# Sheet1.net
KiCad netlist of a schematic drawn in Altium Designer
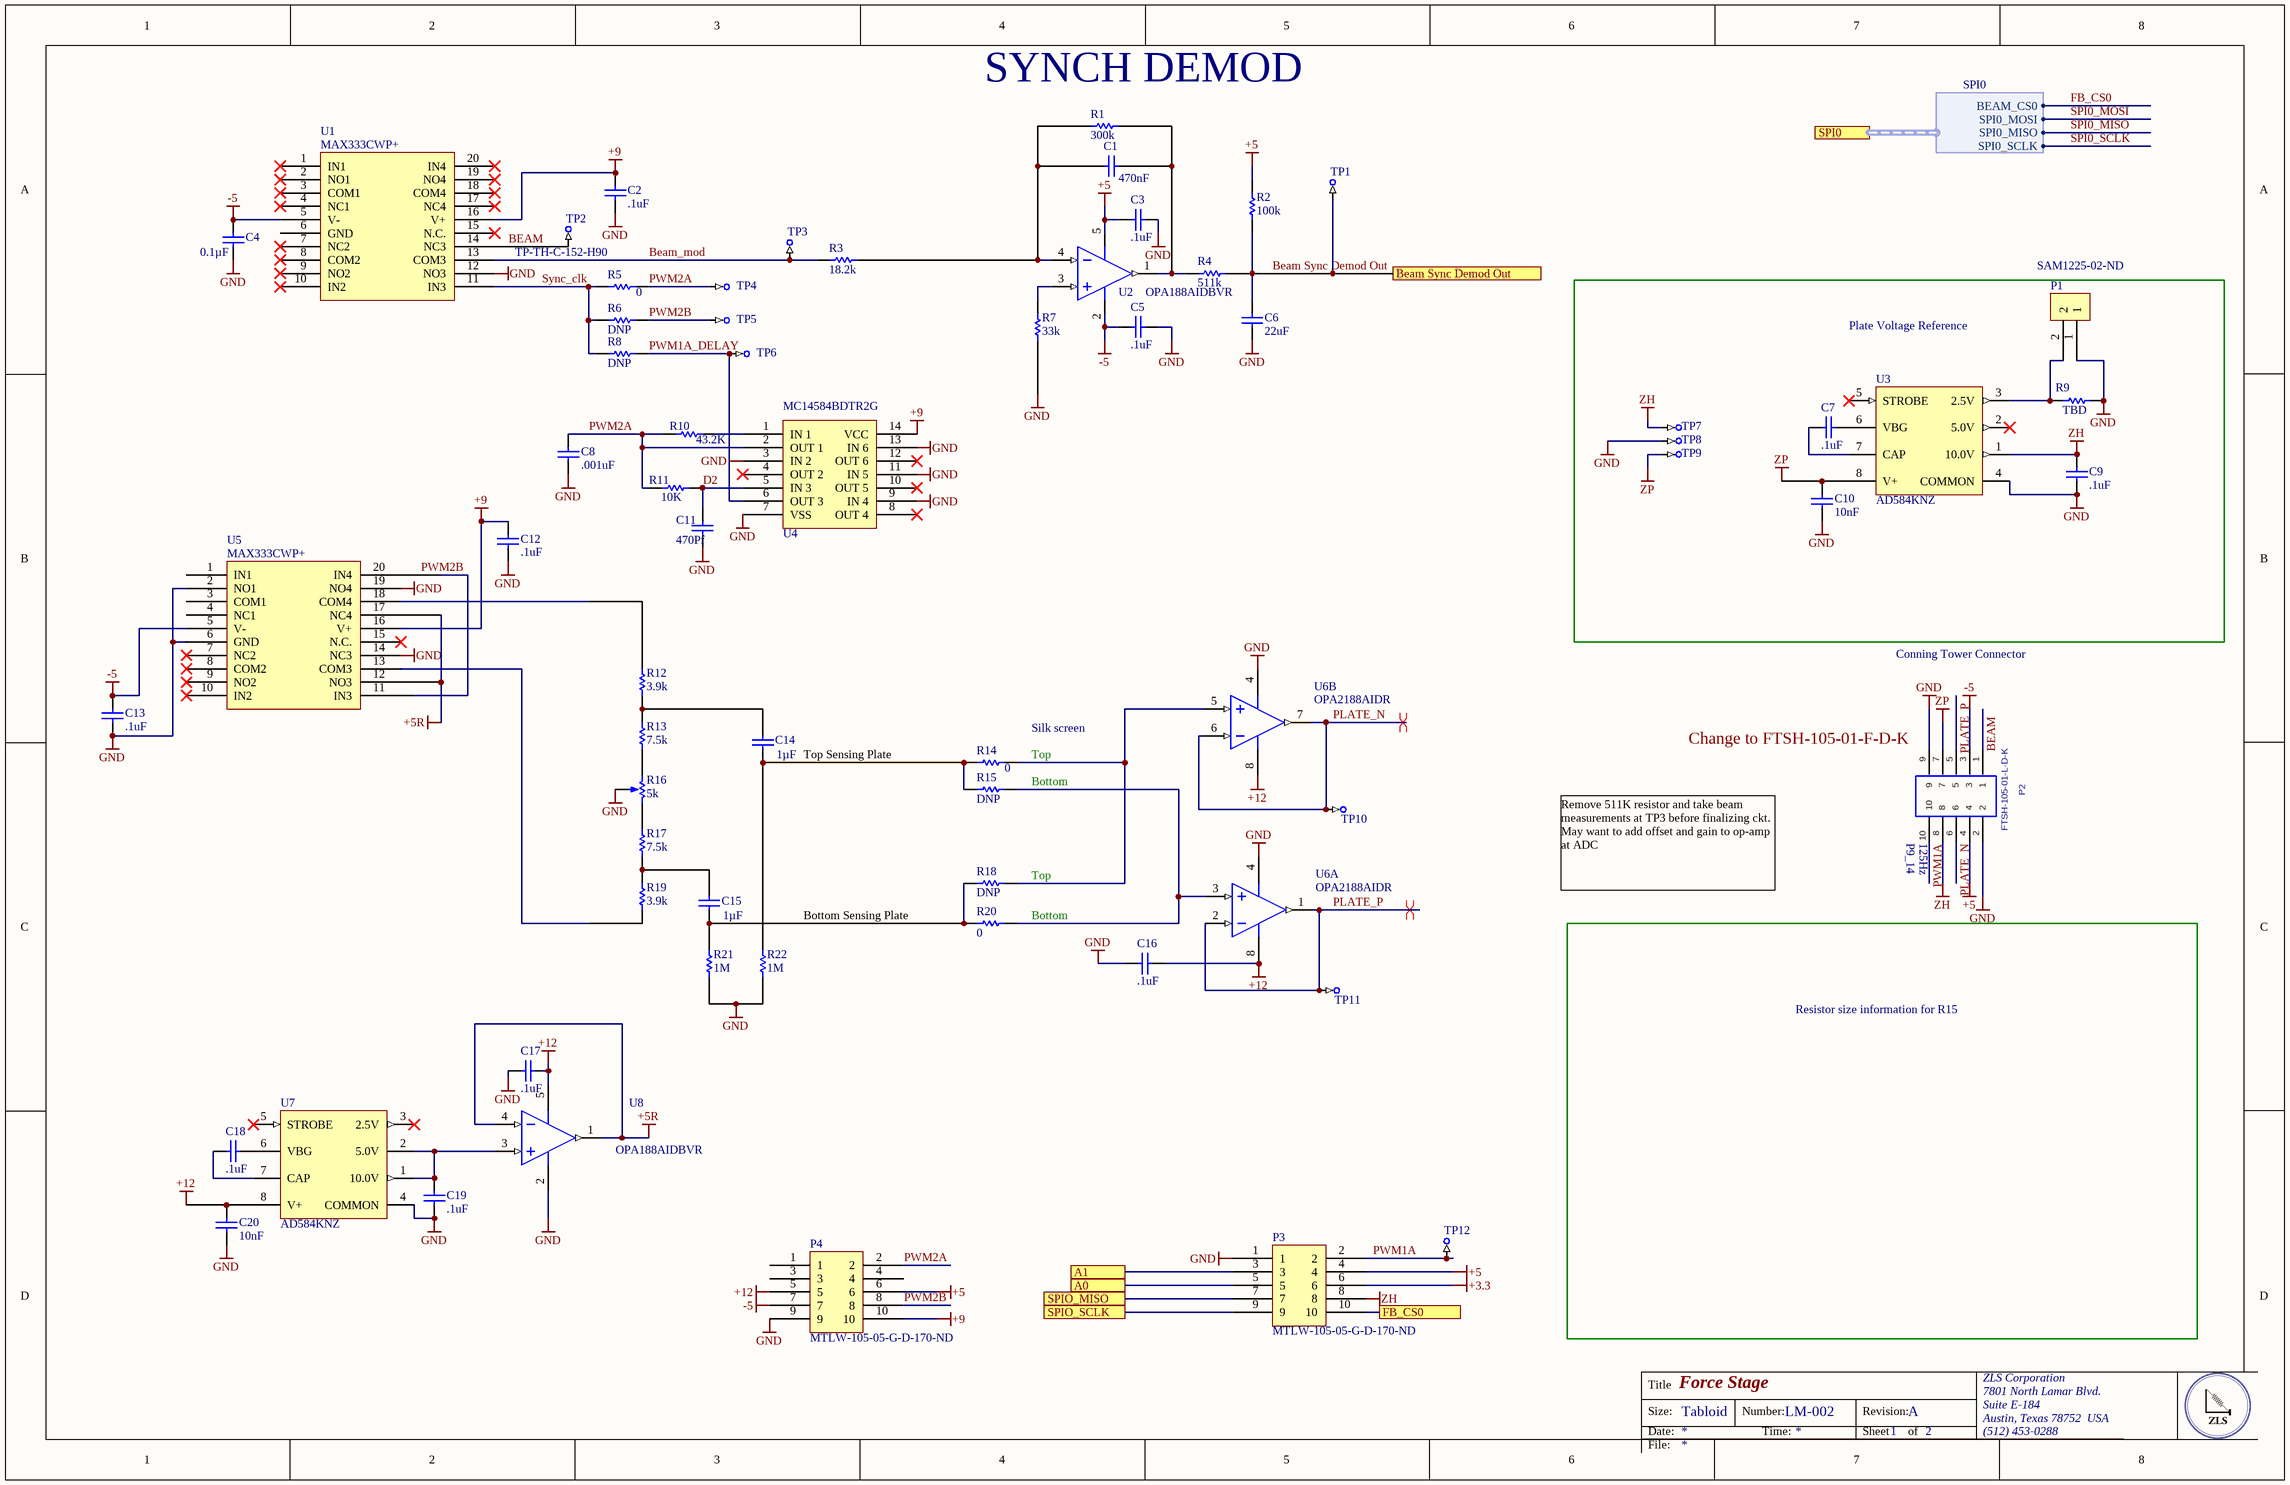
[diagram p0: Sheet1.SchDoc]

(export (version "E")
  (design (tool "Eeschema 10.0.6"))
  (components
    (comp (ref "C1")
      (value "470nF")
      (footprint "CAPC0805(2012)75_L")
      (description "CAP 150pF 16V ±10% 0805 (2012 Metric) Thickness 0.75mm SMD")
      (fields (field (name "TOLERANCE") "Â±10%"))
      (libsource (lib "Altium Content Vault") (part "CMP-1036-02117-1"))
    )
    (comp (ref "C2")
      (value ".1uF")
      (footprint "CAPC0805(2012)75_L")
      (description "CAP 150pF 16V ±10% 0805 (2012 Metric) Thickness 0.75mm SMD")
      (fields (field (name "TOLERANCE") "Â±10%"))
      (libsource (lib "Altium Content Vault") (part "CMP-1036-02117-1"))
    )
    (comp (ref "C3")
      (value ".1uF")
      (footprint "CAPC0805(2012)75_L")
      (description "CAP 150pF 16V ±10% 0805 (2012 Metric) Thickness 0.75mm SMD")
      (fields (field (name "TOLERANCE") "Â±10%"))
      (libsource (lib "Altium Content Vault") (part "CMP-1036-02117-1"))
    )
    (comp (ref "C4")
      (value "CAP CER 0.1UF 25V X7R 0805")
      (footprint "CAPC0805(2012)145_N")
      (fields
        (field (name "MANUFACTURER") "Murata Electronics North America")
        (field (name "MANUFACTURER PART NUMBER") "GRM21BR71E104KA01L")
        (field (name "CAPACITANCE") "0.1µF")
        (field (name "TOLERANCE") "±10%")
      )
      (libsource (lib "Altium Content Vault") (part "CMP-1036-04795-1"))
    )
    (comp (ref "C5")
      (value ".1uF")
      (footprint "CAPC0805(2012)75_L")
      (description "CAP 150pF 16V ±10% 0805 (2012 Metric) Thickness 0.75mm SMD")
      (fields (field (name "TOLERANCE") "Â±10%"))
      (libsource (lib "Altium Content Vault") (part "CMP-1036-02117-1"))
    )
    (comp (ref "C6")
      (value "22uF")
      (footprint "CAPC0805(2012)75_L")
      (description "CAP 150pF 16V ±10% 0805 (2012 Metric) Thickness 0.75mm SMD")
      (fields (field (name "TOLERANCE") "Â±10%"))
      (libsource (lib "Altium Content Vault") (part "CMP-1036-02117-1"))
    )
    (comp (ref "C7")
      (value ".1uF")
      (footprint "CAPC0805(2012)75_M")
      (description "CAP 33pF 25V ±2% 0805 (2012 Metric) Thickness 0.75mm SMD")
      (fields (field (name "TOLERANCE") "Â±2%"))
      (libsource (lib "Altium Content Vault") (part "CMP-1036-01414-1"))
    )
    (comp (ref "C8")
      (value ".001uF")
      (footprint "CAPC0805(2012)75_L")
      (description "CAP 150pF 16V ±10% 0805 (2012 Metric) Thickness 0.75mm SMD")
      (fields (field (name "TOLERANCE") "Â±10%"))
      (libsource (lib "Altium Content Vault") (part "CMP-1036-02117-1"))
    )
    (comp (ref "C9")
      (value ".1uF")
      (footprint "CAPC0805(2012)75_M")
      (description "CAP 33pF 25V ±2% 0805 (2012 Metric) Thickness 0.75mm SMD")
      (fields (field (name "TOLERANCE") "Â±2%"))
      (libsource (lib "Altium Content Vault") (part "CMP-1036-01414-1"))
    )
    (comp (ref "C10")
      (value "Multilayer Ceramic Capacitors MLCC - SMD/SMT 0.01uF 50volts 10% X7R")
      (footprint "CAPC0805(2012)145_N")
      (fields
        (field (name "MANUFACTURER") "Kemet")
        (field (name "MANUFACTURER PART NUMBER") "C0805C103K5RACAUTO")
        (field (name "CAPACITANCE") "10nF")
        (field (name "TOLERANCE") "10%")
      )
      (libsource (lib "Altium Content Vault") (part "CMP-1036-04795-1"))
    )
    (comp (ref "C11")
      (value "470Pf")
      (footprint "CAPC0805(2012)75_L")
      (description "CAP 150pF 16V ±10% 0805 (2012 Metric) Thickness 0.75mm SMD")
      (fields (field (name "TOLERANCE") "Â±10%"))
      (libsource (lib "Altium Content Vault") (part "CMP-1036-02117-1"))
    )
    (comp (ref "C12")
      (value ".1uF")
      (footprint "CAPC0805(2012)75_M")
      (description "CAP 33pF 25V ±2% 0805 (2012 Metric) Thickness 0.75mm SMD")
      (fields (field (name "TOLERANCE") "Â±2%"))
      (libsource (lib "Altium Content Vault") (part "CMP-1036-01414-1"))
    )
    (comp (ref "C13")
      (value ".1uF")
      (footprint "CAPC0805(2012)75_M")
      (description "CAP 33pF 25V ±2% 0805 (2012 Metric) Thickness 0.75mm SMD")
      (fields (field (name "TOLERANCE") "Â±2%"))
      (libsource (lib "Altium Content Vault") (part "CMP-1036-01414-1"))
    )
    (comp (ref "C14")
      (value "CAP CER 1UF 25V X7R 0805")
      (footprint "CAPC0805(2012)155_L")
      (fields
        (field (name "MANUFACTURER") "Murata Electronics North America")
        (field (name "MANUFACTURER PART NUMBER") "GRM21BR71E105KA99L")
        (field (name "CAPACITANCE") "1µF")
        (field (name "TOLERANCE") "±10%")
      )
      (libsource (lib "Altium Content Vault") (part "CMP-1036-04882-1"))
    )
    (comp (ref "C15")
      (value "CAP CER 1UF 25V X7R 0805")
      (footprint "CAPC0805(2012)155_L")
      (fields
        (field (name "MANUFACTURER") "Murata Electronics North America")
        (field (name "MANUFACTURER PART NUMBER") "GRM21BR71E105KA99L")
        (field (name "CAPACITANCE") "1µF")
        (field (name "TOLERANCE") "±10%")
      )
      (libsource (lib "Altium Content Vault") (part "CMP-1036-04882-1"))
    )
    (comp (ref "C16")
      (value ".1uF")
      (footprint "CAPC0805(2012)75_M")
      (description "CAP 33pF 25V ±2% 0805 (2012 Metric) Thickness 0.75mm SMD")
      (fields (field (name "TOLERANCE") "Â±2%"))
      (libsource (lib "Altium Content Vault") (part "CMP-1036-01414-1"))
    )
    (comp (ref "C17")
      (value ".1uF")
      (footprint "CAPC0805(2012)75_M")
      (description "CAP 33pF 25V ±2% 0805 (2012 Metric) Thickness 0.75mm SMD")
      (fields (field (name "TOLERANCE") "Â±2%"))
      (libsource (lib "Altium Content Vault") (part "CMP-1036-01414-1"))
    )
    (comp (ref "C18")
      (value ".1uF")
      (footprint "CAPC0805(2012)75_M")
      (description "CAP 33pF 25V ±2% 0805 (2012 Metric) Thickness 0.75mm SMD")
      (fields (field (name "TOLERANCE") "Â±2%"))
      (libsource (lib "Altium Content Vault") (part "CMP-1036-01414-1"))
    )
    (comp (ref "C19")
      (value ".1uF")
      (footprint "CAPC0805(2012)75_M")
      (description "CAP 33pF 25V ±2% 0805 (2012 Metric) Thickness 0.75mm SMD")
      (fields (field (name "TOLERANCE") "Â±2%"))
      (libsource (lib "Altium Content Vault") (part "CMP-1036-01414-1"))
    )
    (comp (ref "C20")
      (value "Multilayer Ceramic Capacitors MLCC - SMD/SMT 0.01uF 50volts 10% X7R")
      (footprint "CAPC0805(2012)145_N")
      (fields
        (field (name "MANUFACTURER") "Kemet")
        (field (name "MANUFACTURER PART NUMBER") "C0805C103K5RACAUTO")
        (field (name "CAPACITANCE") "10nF")
        (field (name "TOLERANCE") "10%")
      )
      (libsource (lib "Altium Content Vault") (part "CMP-1036-04795-1"))
    )
    (comp (ref "P1")
      (value "SSW-102-02-G-S-RA")
      (footprint "SSW-102-02-G-S-RA")
      (fields (field (name "SUPPLIER PART NUMBER 1") "SAM1225-02-ND"))
      (libsource (lib "ZLS_Schematic_lib") (part "SSW-102-02-G-S-RA"))
    )
    (comp (ref "P2")
      (value "FTSH-105-01-L-D-K")
      (footprint "FTSH-105-01-XXX-D-K")
      (description "TERMINAL STRIP, .050\"(1.27mm) PITCH, 10 PINS, KEYING OPTION.")
      (fields
        (field (name "MANUFACTURER") "SAMTEC")
        (field (name "CREATED") "September 26, 2016 - Wendy Xin")
      )
      (libsource (lib "FTSH-105-01-XXX-D-K") (part "FTSH-105-01-XXX-D-K"))
    )
    (comp (ref "P3")
      (value "TLW-105-05-G-D")
      (footprint "TLW-105-05-G-D")
      (fields
        (field (name "SUPPLIER PART NUMBER 1") "MTLW-105-05-G-D-170-ND")
        (field (name "MANUFACTURER") "Samtec Inc.")
        (field (name "MANUFACTURER PART NUMBER") "MTLW-105-05-G-D-170")
      )
      (libsource (lib "ZLS_Schematic_lib") (part "TLW-105-05-G-D"))
    )
    (comp (ref "P4")
      (value "TLW-105-05-G-D")
      (footprint "TLW-105-05-G-D")
      (fields
        (field (name "SUPPLIER PART NUMBER 1") "MTLW-105-05-G-D-170-ND")
        (field (name "MANUFACTURER") "Samtec Inc.")
        (field (name "MANUFACTURER PART NUMBER") "MTLW-105-05-G-D-170")
      )
      (libsource (lib "ZLS_Schematic_lib") (part "TLW-105-05-G-D"))
    )
    (comp (ref "R1")
      (value "300k")
      (footprint "RESC0805(2012)_L")
      (description "2R55 0.125W 1% 0805 (2012 Metric)  SMD")
      (fields (field (name "TOLERANCE") "1 %") (field (name "POWER") "0.125 W"))
      (libsource (lib "Altium Content Vault") (part "CMP-1013-00215-1"))
    )
    (comp (ref "R2")
      (value "100k")
      (footprint "RESC0805(2012)_L")
      (description "2R55 0.125W 1% 0805 (2012 Metric)  SMD")
      (fields (field (name "TOLERANCE") "1 %") (field (name "POWER") "0.125 W"))
      (libsource (lib "Altium Content Vault") (part "CMP-1013-00215-1"))
    )
    (comp (ref "R3")
      (value "18.2k")
      (footprint "RESC0805(2012)_L")
      (description "2R55 0.125W 1% 0805 (2012 Metric)  SMD")
      (fields (field (name "TOLERANCE") "1 %") (field (name "POWER") "0.125 W"))
      (libsource (lib "Altium Content Vault") (part "CMP-1013-00215-1"))
    )
    (comp (ref "R4")
      (value "511k")
      (footprint "RESC0805(2012)_L")
      (description "2R55 0.125W 1% 0805 (2012 Metric)  SMD")
      (fields (field (name "TOLERANCE") "1 %") (field (name "POWER") "0.125 W"))
      (libsource (lib "Altium Content Vault") (part "CMP-1013-00215-1"))
    )
    (comp (ref "R5")
      (value "0")
      (footprint "RESC0805(2012)_L")
      (description "2R55 0.125W 1% 0805 (2012 Metric)  SMD")
      (fields (field (name "TOLERANCE") "1 %") (field (name "POWER") "0.125 W"))
      (libsource (lib "Altium Content Vault") (part "CMP-1013-00215-1"))
    )
    (comp (ref "R6")
      (value "DNP")
      (footprint "RESC0805(2012)_L")
      (description "2R55 0.125W 1% 0805 (2012 Metric)  SMD")
      (fields (field (name "TOLERANCE") "1 %") (field (name "POWER") "0.125 W"))
      (libsource (lib "Altium Content Vault") (part "CMP-1013-00215-1"))
    )
    (comp (ref "R7")
      (value "33k")
      (footprint "RESC0805(2012)_L")
      (description "2R55 0.125W 1% 0805 (2012 Metric)  SMD")
      (fields (field (name "TOLERANCE") "1 %") (field (name "POWER") "0.125 W"))
      (libsource (lib "Altium Content Vault") (part "CMP-1013-00215-1"))
    )
    (comp (ref "R8")
      (value "DNP")
      (footprint "RESC0805(2012)_L")
      (description "2R55 0.125W 1% 0805 (2012 Metric)  SMD")
      (fields (field (name "TOLERANCE") "1 %") (field (name "POWER") "0.125 W"))
      (libsource (lib "Altium Content Vault") (part "CMP-1013-00215-1"))
    )
    (comp (ref "R9")
      (value "TBD")
      (footprint "VH102K")
      (libsource (lib "altium-import") (part "root_0_CMP-1013-00393-1_"))
    )
    (comp (ref "R10")
      (value "43.2K")
      (footprint "RESC0805(2012)_L")
      (description "2R55 0.125W 1% 0805 (2012 Metric)  SMD")
      (fields (field (name "TOLERANCE") "1 %") (field (name "POWER") "0.125 W"))
      (libsource (lib "Altium Content Vault") (part "CMP-1013-00215-1"))
    )
    (comp (ref "R11")
      (value "10K")
      (footprint "RESC0805(2012)_L")
      (description "2R55 0.125W 1% 0805 (2012 Metric)  SMD")
      (fields (field (name "TOLERANCE") "1 %") (field (name "POWER") "0.125 W"))
      (libsource (lib "Altium Content Vault") (part "CMP-1013-00215-1"))
    )
    (comp (ref "R12")
      (value "3.9k")
      (footprint "RESC0805(2012)_L")
      (description "2R55 0.125W 1% 0805 (2012 Metric)  SMD")
      (fields (field (name "TOLERANCE") "1 %") (field (name "POWER") "0.125 W"))
      (libsource (lib "Altium Content Vault") (part "CMP-1013-00215-1"))
    )
    (comp (ref "R13")
      (value "7.5k")
      (footprint "RESC0805(2012)_L")
      (description "2R55 0.125W 1% 0805 (2012 Metric)  SMD")
      (fields (field (name "TOLERANCE") "1 %") (field (name "POWER") "0.125 W"))
      (libsource (lib "Altium Content Vault") (part "CMP-1013-00215-1"))
    )
    (comp (ref "R14")
      (value "0")
      (footprint "RESC0805(2012)_L")
      (description "2R55 0.125W 1% 0805 (2012 Metric)  SMD")
      (fields (field (name "TOLERANCE") "1 %") (field (name "POWER") "0.125 W"))
      (libsource (lib "Altium Content Vault") (part "CMP-1013-00215-1"))
    )
    (comp (ref "R15")
      (value "DNP")
      (footprint "RESC0805(2012)_L")
      (description "2R55 0.125W 1% 0805 (2012 Metric)  SMD")
      (fields (field (name "TOLERANCE") "1 %") (field (name "POWER") "0.125 W"))
      (libsource (lib "Altium Content Vault") (part "CMP-1013-00215-1"))
    )
    (comp (ref "R16")
      (value "TRIMMER 5K OHM 0.25W PC PIN")
      (footprint "Trimmer 2.54")
      (fields
        (field (name "MANUFACTURER") "Vishay Foil Resistors (Division of Vishay Precision Group)")
        (field (name "MANUFACTURER PART NUMBER") "Y00535K00000J0L")
        (field (name "RESISTANCE (OHMS)") "5k")
        (field (name "TOLERANCE") "±5%")
      )
      (libsource (lib "ZLS_Schematic_lib") (part "Trimmer"))
    )
    (comp (ref "R17")
      (value "7.5k")
      (footprint "RESC0805(2012)_L")
      (description "2R55 0.125W 1% 0805 (2012 Metric)  SMD")
      (fields (field (name "TOLERANCE") "1 %") (field (name "POWER") "0.125 W"))
      (libsource (lib "Altium Content Vault") (part "CMP-1013-00215-1"))
    )
    (comp (ref "R18")
      (value "DNP")
      (footprint "RESC0805(2012)_L")
      (description "2R55 0.125W 1% 0805 (2012 Metric)  SMD")
      (fields (field (name "TOLERANCE") "1 %") (field (name "POWER") "0.125 W"))
      (libsource (lib "Altium Content Vault") (part "CMP-1013-00215-1"))
    )
    (comp (ref "R19")
      (value "3.9k")
      (footprint "RESC0805(2012)_L")
      (description "2R55 0.125W 1% 0805 (2012 Metric)  SMD")
      (fields (field (name "TOLERANCE") "1 %") (field (name "POWER") "0.125 W"))
      (libsource (lib "Altium Content Vault") (part "CMP-1013-00215-1"))
    )
    (comp (ref "R20")
      (value "0")
      (footprint "RESC0805(2012)_L")
      (description "2R55 0.125W 1% 0805 (2012 Metric)  SMD")
      (fields (field (name "TOLERANCE") "1 %") (field (name "POWER") "0.125 W"))
      (libsource (lib "Altium Content Vault") (part "CMP-1013-00215-1"))
    )
    (comp (ref "R21")
      (value "1M")
      (footprint "RESC0805(2012)_L")
      (description "2R55 0.125W 1% 0805 (2012 Metric)  SMD")
      (fields (field (name "TOLERANCE") "1 %") (field (name "POWER") "0.125 W"))
      (libsource (lib "Altium Content Vault") (part "CMP-1013-00215-1"))
    )
    (comp (ref "R22")
      (value "1M")
      (footprint "RESC0805(2012)_L")
      (description "2R55 0.125W 1% 0805 (2012 Metric)  SMD")
      (fields (field (name "TOLERANCE") "1 %") (field (name "POWER") "0.125 W"))
      (libsource (lib "Altium Content Vault") (part "CMP-1013-00215-1"))
    )
    (comp (ref "TP1")
      (value "TP-TH-C-152-H90")
      (footprint "TP-TH-C-152-H90")
      (description "Test Point, Through Hole, Hole Size 0.9 mm, PCB Mount with Silkscreen Box")
      (fields (field (name "MANUFACTURER") "No Vendor"))
      (libsource (lib "Altium Content Vault") (part "CMP-0484-00003-2"))
    )
    (comp (ref "TP2")
      (value "TP-TH-C-152-H90")
      (footprint "TP-TH-C-152-H90")
      (description "Test Point, Through Hole, Hole Size 0.9 mm, PCB Mount with Silkscreen Box")
      (fields (field (name "MANUFACTURER") "No Vendor"))
      (libsource (lib "Altium Content Vault") (part "TP-TH"))
    )
    (comp (ref "TP3")
      (value "TP-TH-C-152-H90")
      (footprint "TP-TH-C-152-H90")
      (description "Test Point, Through Hole, Hole Size 0.9 mm, PCB Mount with Silkscreen Box")
      (fields (field (name "MANUFACTURER") "No Vendor"))
      (libsource (lib "Altium Content Vault") (part "CMP-0484-00003-2"))
    )
    (comp (ref "TP4")
      (value "TP-TH-C-152-H90")
      (footprint "TP-TH-C-152-H90")
      (description "Test Point, Through Hole, Hole Size 0.9 mm, PCB Mount with Silkscreen Box")
      (fields (field (name "MANUFACTURER") "No Vendor"))
      (libsource (lib "Altium Content Vault") (part "CMP-0484-00003-2"))
    )
    (comp (ref "TP5")
      (value "TP-TH-C-152-H90")
      (footprint "TP-TH-C-152-H90")
      (description "Test Point, Through Hole, Hole Size 0.9 mm, PCB Mount with Silkscreen Box")
      (fields (field (name "MANUFACTURER") "No Vendor"))
      (libsource (lib "Altium Content Vault") (part "CMP-0484-00003-2"))
    )
    (comp (ref "TP6")
      (value "TP-TH-C-152-H90")
      (footprint "TP-TH-C-152-H90")
      (description "Test Point, Through Hole, Hole Size 0.9 mm, PCB Mount with Silkscreen Box")
      (fields (field (name "MANUFACTURER") "No Vendor"))
      (libsource (lib "Altium Content Vault") (part "CMP-0484-00003-2"))
    )
    (comp (ref "TP7")
      (value "TP-TH-C-152-H90")
      (footprint "TP-TH-C-152-H90")
      (description "Test Point, Through Hole, Hole Size 0.9 mm, PCB Mount with Silkscreen Box")
      (fields (field (name "MANUFACTURER") "No Vendor"))
      (libsource (lib "Altium Content Vault") (part "CMP-0484-00003-2"))
    )
    (comp (ref "TP8")
      (value "TP-TH-C-152-H90")
      (footprint "TP-TH-C-152-H90")
      (description "Test Point, Through Hole, Hole Size 0.9 mm, PCB Mount with Silkscreen Box")
      (fields (field (name "MANUFACTURER") "No Vendor"))
      (libsource (lib "Altium Content Vault") (part "CMP-0484-00003-2"))
    )
    (comp (ref "TP9")
      (value "TP-TH-C-152-H90")
      (footprint "TP-TH-C-152-H90")
      (description "Test Point, Through Hole, Hole Size 0.9 mm, PCB Mount with Silkscreen Box")
      (fields (field (name "MANUFACTURER") "No Vendor"))
      (libsource (lib "Altium Content Vault") (part "CMP-0484-00003-2"))
    )
    (comp (ref "TP10")
      (value "TP-TH-C-152-H90")
      (footprint "TP-TH-C-152-H90")
      (description "Test Point, Through Hole, Hole Size 0.9 mm, PCB Mount with Silkscreen Box")
      (fields (field (name "MANUFACTURER") "No Vendor"))
      (libsource (lib "Altium Content Vault") (part "CMP-0484-00003-2"))
    )
    (comp (ref "TP11")
      (value "TP-TH-C-152-H90")
      (footprint "TP-TH-C-152-H90")
      (description "Test Point, Through Hole, Hole Size 0.9 mm, PCB Mount with Silkscreen Box")
      (fields (field (name "MANUFACTURER") "No Vendor"))
      (libsource (lib "Altium Content Vault") (part "CMP-0484-00003-2"))
    )
    (comp (ref "TP12")
      (value "TP-TH-C-152-H90")
      (footprint "TP-TH-C-152-H90")
      (description "Test Point, Through Hole, Hole Size 0.9 mm, PCB Mount with Silkscreen Box")
      (fields (field (name "MANUFACTURER") "No Vendor"))
      (libsource (lib "Altium Content Vault") (part "CMP-0484-00003-2"))
    )
    (comp (ref "U1")
      (value "MAX333CWP+")
      (footprint "TSOP65P640X90-20N")
      (description "IC SWITCH QUAD SPDT 20TSSOP")
      (fields (field (name "MANUFACTURER") "Maxim") (field (name "MANUFACTURER PART NUMBER") "MAX333AEUP+"))
      (libsource (lib "ZLS_Schematic_lib") (part "MAX333CWP+"))
    )
    (comp (ref "U2")
      (value "OPA188AIDBVR")
      (footprint "DBV0005A_M")
      (fields (field (name "MANUFACTURER") "Texas Instruments"))
      (libsource (lib "Altium Content Vault") (part "CMP-0809-00005-2"))
    )
    (comp (ref "U3")
      (value "AD584KNZ")
      (footprint "ADI-N-8")
      (fields (field (name "MANUFACTURER") "Analog Devices"))
      (libsource (lib "Altium Content Vault") (part "ADI-AD584-N-8"))
    )
    (comp (ref "U4")
      (value "MC14584BDTR2G")
      (footprint "MC14584BDTR2G")
      (fields (field (name "MANUFACTURER") "ON Semiconductor") (field (name "BASE PART NUMBER") "4584"))
      (libsource (lib "ZLS_Schematic_lib") (part "MC14584BDTR2G"))
    )
    (comp (ref "U5")
      (value "MAX333CWP+")
      (footprint "TSOP65P640X90-20N")
      (description "IC SWITCH QUAD SPDT 20TSSOP")
      (fields (field (name "MANUFACTURER") "Maxim") (field (name "MANUFACTURER PART NUMBER") "MAX333AEUP+"))
      (libsource (lib "ZLS_Schematic_lib") (part "MAX333CWP+"))
    )
    (comp (ref "U6")
      (value "OPA2188AIDR")
      (footprint "D0008A_L")
      (fields (field (name "MANUFACTURER") "Texas Instruments"))
      (libsource (lib "Altium Content Vault") (part "CMP-0272-00241-3"))
    )
    (comp (ref "U7")
      (value "AD584KNZ")
      (footprint "ADI-N-8")
      (fields (field (name "MANUFACTURER") "Analog Devices"))
      (libsource (lib "Altium Content Vault") (part "CMP-0784-00054-1"))
    )
    (comp (ref "U8")
      (value "OPA188AIDBVR")
      (footprint "DBV0005A_M")
      (fields (field (name "MANUFACTURER") "Texas Instruments"))
      (libsource (lib "Altium Content Vault") (part "CMP-0809-00005-2"))
    )
  )
  (nets
    (net (code "2") (name "+3.3") (class "Default")
      (node (ref "P3") (pin "6") (pinfunction "6_6") (pintype "passive"))
    )
    (net (code "3") (name "+5") (class "Default")
      (node (ref "C3") (pin "1") (pinfunction "1_1") (pintype "passive"))
      (node (ref "P2") (pin "4") (pinfunction "4_4") (pintype "passive"))
      (node (ref "P3") (pin "4") (pinfunction "4_4") (pintype "passive"))
      (node (ref "P4") (pin "6") (pinfunction "6_6") (pintype "passive"))
      (node (ref "R2") (pin "2") (pinfunction "2_2") (pintype "passive"))
      (node (ref "U2") (pin "5") (pinfunction "V+_5") (pintype "power_in"))
    )
    (net (code "4") (name "+5R") (class "Default")
      (node (ref "U5") (pin "12") (pinfunction "NO3_12") (pintype "passive"))
      (node (ref "U5") (pin "17") (pinfunction "NC4_17") (pintype "passive"))
      (node (ref "U8") (pin "1") (pinfunction "OUT_1") (pintype "output"))
      (node (ref "U8") (pin "4") (pinfunction "IN-_4") (pintype "input"))
    )
    (net (code "5") (name "+9") (class "Default")
      (node (ref "C12") (pin "2") (pinfunction "2_2") (pintype "passive"))
      (node (ref "C2") (pin "2") (pinfunction "2_2") (pintype "passive"))
      (node (ref "P4") (pin "10") (pinfunction "10_10") (pintype "passive"))
      (node (ref "U1") (pin "16") (pinfunction "V+_16") (pintype "power_in"))
      (node (ref "U4") (pin "14") (pinfunction "VCC_14") (pintype "passive"))
      (node (ref "U5") (pin "16") (pinfunction "V+_16") (pintype "power_in"))
    )
    (net (code "6") (name "+12") (class "Default")
      (node (ref "C16") (pin "2") (pinfunction "2_2") (pintype "passive"))
      (node (ref "C17") (pin "2") (pinfunction "2_2") (pintype "passive"))
      (node (ref "C20") (pin "1") (pinfunction "1_1") (pintype "passive"))
      (node (ref "P4") (pin "5") (pinfunction "5_5") (pintype "passive"))
      (node (ref "U6") (pin "8") (pinfunction "V+_8") (pintype "power_in"))
      (node (ref "U7") (pin "8") (pinfunction "V+_8") (pintype "power_in"))
      (node (ref "U8") (pin "5") (pinfunction "V+_5") (pintype "power_in"))
    )
    (net (code "7") (name "-5") (class "Default")
      (node (ref "C13") (pin "2") (pinfunction "2_2") (pintype "passive"))
      (node (ref "C4") (pin "1") (pinfunction "1_1") (pintype "passive"))
      (node (ref "C5") (pin "1") (pinfunction "1_1") (pintype "passive"))
      (node (ref "P2") (pin "3") (pinfunction "3_3") (pintype "passive"))
      (node (ref "P4") (pin "7") (pinfunction "7_7") (pintype "passive"))
      (node (ref "U1") (pin "5") (pinfunction "V-_5") (pintype "power_in"))
      (node (ref "U2") (pin "2") (pinfunction "V-_2") (pintype "power_in"))
      (node (ref "U5") (pin "5") (pinfunction "V-_5") (pintype "power_in"))
    )
    (net (code "8") (name "/A0") (class "Default")
      (node (ref "P3") (pin "5") (pinfunction "5_5") (pintype "passive"))
    )
    (net (code "9") (name "/A1") (class "Default")
      (node (ref "P3") (pin "3") (pinfunction "3_3") (pintype "passive"))
    )
    (net (code "10") (name "/BEAM") (class "Default")
      (node (ref "P2") (pin "1") (pinfunction "1_1") (pintype "passive"))
      (node (ref "TP2") (pin "1") (pinfunction "1_1") (pintype "input"))
      (node (ref "U1") (pin "14") (pinfunction "NC3_14") (pintype "passive"))
    )
    (net (code "11") (name "/Beam Sync Demod Out") (class "Default")
      (node (ref "C6") (pin "2") (pinfunction "2_2") (pintype "passive"))
      (node (ref "R2") (pin "1") (pinfunction "1_1") (pintype "passive"))
      (node (ref "R4") (pin "1") (pinfunction "1_1") (pintype "passive"))
      (node (ref "TP1") (pin "1") (pinfunction "1_1") (pintype "input"))
    )
    (net (code "12") (name "/Beam_mod") (class "Default")
      (node (ref "R3") (pin "2") (pinfunction "2_2") (pintype "passive"))
      (node (ref "TP3") (pin "1") (pinfunction "1_1") (pintype "input"))
      (node (ref "U1") (pin "13") (pinfunction "COM3_13") (pintype "passive"))
    )
    (net (code "13") (name "/D2") (class "Default")
      (node (ref "C11") (pin "2") (pinfunction "2_2") (pintype "passive"))
      (node (ref "R11") (pin "1") (pinfunction "1_1") (pintype "passive"))
      (node (ref "U4") (pin "5") (pinfunction "IN_3_5") (pintype "passive"))
    )
    (net (code "14") (name "/FB_CS0") (class "Default")
      (node (ref "P3") (pin "10") (pinfunction "10_10") (pintype "passive"))
    )
    (net (code "15") (name "/PLATE_N") (class "Default")
      (node (ref "P2") (pin "6") (pinfunction "6_6") (pintype "passive"))
      (node (ref "TP10") (pin "1") (pinfunction "1_1") (pintype "input"))
      (node (ref "U6") (pin "6") (pinfunction "IN_B-_6") (pintype "input"))
      (node (ref "U6") (pin "7") (pinfunction "OUT_B_7") (pintype "output"))
    )
    (net (code "16") (name "/PLATE_P") (class "Default")
      (node (ref "P2") (pin "5") (pinfunction "5_5") (pintype "passive"))
      (node (ref "TP11") (pin "1") (pinfunction "1_1") (pintype "input"))
      (node (ref "U6") (pin "1") (pinfunction "OUT_A_1") (pintype "output"))
      (node (ref "U6") (pin "2") (pinfunction "IN_A-_2") (pintype "input"))
    )
    (net (code "17") (name "/PWM1A") (class "Default")
      (node (ref "P2") (pin "10") (pinfunction "10_10") (pintype "passive"))
      (node (ref "P3") (pin "2") (pinfunction "2_2") (pintype "passive"))
      (node (ref "TP12") (pin "1") (pinfunction "1_1") (pintype "input"))
    )
    (net (code "18") (name "/PWM1A_DELAY") (class "Default")
      (node (ref "R8") (pin "1") (pinfunction "1_1") (pintype "passive"))
      (node (ref "TP6") (pin "1") (pinfunction "1_1") (pintype "input"))
      (node (ref "U4") (pin "6") (pinfunction "OUT_3_6") (pintype "passive"))
    )
    (net (code "19") (name "/PWM2A") (class "Default")
      (node (ref "C8") (pin "2") (pinfunction "2_2") (pintype "passive"))
      (node (ref "P4") (pin "2") (pinfunction "2_2") (pintype "passive"))
      (node (ref "R10") (pin "2") (pinfunction "2_2") (pintype "passive"))
      (node (ref "R11") (pin "2") (pinfunction "2_2") (pintype "passive"))
      (node (ref "R5") (pin "1") (pinfunction "1_1") (pintype "passive"))
      (node (ref "TP4") (pin "1") (pinfunction "1_1") (pintype "input"))
      (node (ref "U4") (pin "2") (pinfunction "OUT_1_2") (pintype "passive"))
    )
    (net (code "20") (name "/PWM2B") (class "Default")
      (node (ref "P4") (pin "8") (pinfunction "8_8") (pintype "passive"))
      (node (ref "R6") (pin "1") (pinfunction "1_1") (pintype "passive"))
      (node (ref "TP5") (pin "1") (pinfunction "1_1") (pintype "input"))
      (node (ref "U5") (pin "11") (pinfunction "IN3_11") (pintype "passive"))
      (node (ref "U5") (pin "20") (pinfunction "IN4_20") (pintype "passive"))
    )
    (net (code "24") (name "/SPIO_MISO") (class "Default")
      (node (ref "P3") (pin "7") (pinfunction "7_7") (pintype "passive"))
    )
    (net (code "25") (name "/SPIO_SCLK") (class "Default")
      (node (ref "P3") (pin "9") (pinfunction "9_9") (pintype "passive"))
    )
    (net (code "26") (name "/Sync_clk") (class "Default")
      (node (ref "R5") (pin "2") (pinfunction "2_2") (pintype "passive"))
      (node (ref "R6") (pin "2") (pinfunction "2_2") (pintype "passive"))
      (node (ref "R8") (pin "2") (pinfunction "2_2") (pintype "passive"))
      (node (ref "U1") (pin "11") (pinfunction "IN3_11") (pintype "passive"))
    )
    (net (code "28") (name "GND") (class "Default")
      (node (ref "C10") (pin "2") (pinfunction "2_2") (pintype "passive"))
      (node (ref "C11") (pin "1") (pinfunction "1_1") (pintype "passive"))
      (node (ref "C12") (pin "1") (pinfunction "1_1") (pintype "passive"))
      (node (ref "C13") (pin "1") (pinfunction "1_1") (pintype "passive"))
      (node (ref "C16") (pin "1") (pinfunction "1_1") (pintype "passive"))
      (node (ref "C17") (pin "1") (pinfunction "1_1") (pintype "passive"))
      (node (ref "C19") (pin "1") (pinfunction "1_1") (pintype "passive"))
      (node (ref "C2") (pin "1") (pinfunction "1_1") (pintype "passive"))
      (node (ref "C20") (pin "2") (pinfunction "2_2") (pintype "passive"))
      (node (ref "C3") (pin "2") (pinfunction "2_2") (pintype "passive"))
      (node (ref "C4") (pin "2") (pinfunction "2_2") (pintype "passive"))
      (node (ref "C5") (pin "2") (pinfunction "2_2") (pintype "passive"))
      (node (ref "C6") (pin "1") (pinfunction "1_1") (pintype "passive"))
      (node (ref "C8") (pin "1") (pinfunction "1_1") (pintype "passive"))
      (node (ref "C9") (pin "1") (pinfunction "1_1") (pintype "passive"))
      (node (ref "P1") (pin "1") (pinfunction "1_1") (pintype "passive"))
      (node (ref "P2") (pin "2") (pinfunction "2_2") (pintype "passive"))
      (node (ref "P2") (pin "9") (pinfunction "9_9") (pintype "passive"))
      (node (ref "P3") (pin "1") (pinfunction "1_1") (pintype "passive"))
      (node (ref "P4") (pin "9") (pinfunction "9_9") (pintype "passive"))
      (node (ref "R16") (pin "2") (pinfunction "b_2") (pintype "passive"))
      (node (ref "R21") (pin "1") (pinfunction "1_1") (pintype "passive"))
      (node (ref "R22") (pin "1") (pinfunction "1_1") (pintype "passive"))
      (node (ref "R7") (pin "1") (pinfunction "1_1") (pintype "passive"))
      (node (ref "R9") (pin "2") (pinfunction "2_2") (pintype "passive"))
      (node (ref "TP8") (pin "1") (pinfunction "1_1") (pintype "input"))
      (node (ref "U1") (pin "12") (pinfunction "NO3_12") (pintype "passive"))
      (node (ref "U3") (pin "4") (pinfunction "COMMON_4") (pintype "passive"))
      (node (ref "U4") (pin "11") (pinfunction "IN_5_11") (pintype "passive"))
      (node (ref "U4") (pin "13") (pinfunction "IN_6_13") (pintype "passive"))
      (node (ref "U4") (pin "3") (pinfunction "IN_2_3") (pintype "passive"))
      (node (ref "U4") (pin "7") (pinfunction "VSS_7") (pintype "passive"))
      (node (ref "U4") (pin "9") (pinfunction "IN_4_9") (pintype "passive"))
      (node (ref "U5") (pin "14") (pinfunction "NC3_14") (pintype "passive"))
      (node (ref "U5") (pin "19") (pinfunction "NO4_19") (pintype "passive"))
      (node (ref "U5") (pin "2") (pinfunction "NO1_2") (pintype "passive"))
      (node (ref "U5") (pin "6") (pinfunction "GND_6") (pintype "passive"))
      (node (ref "U6") (pin "4") (pinfunction "V-_4") (pintype "power_in"))
      (node (ref "U7") (pin "4") (pinfunction "COMMON_4") (pintype "passive"))
      (node (ref "U8") (pin "2") (pinfunction "V-_2") (pintype "power_in"))
    )
    (net (code "29") (name "Net-(C14-Pad1)") (class "Default")
      (node (ref "C14") (pin "1") (pinfunction "1_1") (pintype "passive"))
      (node (ref "R14") (pin "2") (pinfunction "2_2") (pintype "passive"))
      (node (ref "R15") (pin "2") (pinfunction "2_2") (pintype "passive"))
      (node (ref "R22") (pin "2") (pinfunction "2_2") (pintype "passive"))
    )
    (net (code "30") (name "Net-(C14-Pad2)") (class "Default")
      (node (ref "C14") (pin "2") (pinfunction "2_2") (pintype "passive"))
      (node (ref "R12") (pin "1") (pinfunction "1_1") (pintype "passive"))
      (node (ref "R13") (pin "2") (pinfunction "2_2") (pintype "passive"))
    )
    (net (code "31") (name "Net-(C15-Pad1)") (class "Default")
      (node (ref "C15") (pin "1") (pinfunction "1_1") (pintype "passive"))
      (node (ref "R18") (pin "2") (pinfunction "2_2") (pintype "passive"))
      (node (ref "R20") (pin "2") (pinfunction "2_2") (pintype "passive"))
      (node (ref "R21") (pin "2") (pinfunction "2_2") (pintype "passive"))
    )
    (net (code "32") (name "Net-(C15-Pad2)") (class "Default")
      (node (ref "C15") (pin "2") (pinfunction "2_2") (pintype "passive"))
      (node (ref "R17") (pin "1") (pinfunction "1_1") (pintype "passive"))
      (node (ref "R19") (pin "2") (pinfunction "2_2") (pintype "passive"))
    )
    (net (code "33") (name "Net-(R16-a)") (class "Default")
      (node (ref "R13") (pin "1") (pinfunction "1_1") (pintype "passive"))
      (node (ref "R16") (pin "1") (pinfunction "a_1") (pintype "passive"))
    )
    (net (code "34") (name "Net-(R16-c)") (class "Default")
      (node (ref "R16") (pin "3") (pinfunction "c_3") (pintype "passive"))
      (node (ref "R17") (pin "2") (pinfunction "2_2") (pintype "passive"))
    )
    (net (code "35") (name "Net-(U2-IN+)") (class "Default")
      (node (ref "R7") (pin "2") (pinfunction "2_2") (pintype "passive"))
      (node (ref "U2") (pin "3") (pinfunction "IN+_3") (pintype "input"))
    )
    (net (code "36") (name "Net-(U2-IN-)") (class "Default")
      (node (ref "C1") (pin "1") (pinfunction "1_1") (pintype "passive"))
      (node (ref "R1") (pin "2") (pinfunction "2_2") (pintype "passive"))
      (node (ref "R3") (pin "1") (pinfunction "1_1") (pintype "passive"))
      (node (ref "U2") (pin "4") (pinfunction "IN-_4") (pintype "input"))
    )
    (net (code "37") (name "Net-(U2-OUT)") (class "Default")
      (node (ref "C1") (pin "2") (pinfunction "2_2") (pintype "passive"))
      (node (ref "R1") (pin "1") (pinfunction "1_1") (pintype "passive"))
      (node (ref "R4") (pin "2") (pinfunction "2_2") (pintype "passive"))
      (node (ref "U2") (pin "1") (pinfunction "OUT_1") (pintype "output"))
    )
    (net (code "38") (name "Net-(U3-2.5V)") (class "Default")
      (node (ref "P1") (pin "2") (pinfunction "2_2") (pintype "passive"))
      (node (ref "R9") (pin "1") (pinfunction "1_1") (pintype "passive"))
      (node (ref "U3") (pin "3") (pinfunction "2.5V_3") (pintype "output"))
    )
    (net (code "39") (name "Net-(U3-CAP)") (class "Default")
      (node (ref "C7") (pin "1") (pinfunction "1_1") (pintype "passive"))
      (node (ref "U3") (pin "7") (pinfunction "CAP_7") (pintype "passive"))
    )
    (net (code "40") (name "Net-(U3-VBG)") (class "Default")
      (node (ref "C7") (pin "2") (pinfunction "2_2") (pintype "passive"))
      (node (ref "U3") (pin "6") (pinfunction "VBG_6") (pintype "passive"))
    )
    (net (code "41") (name "Net-(U4-IN_1)") (class "Default")
      (node (ref "R10") (pin "1") (pinfunction "1_1") (pintype "passive"))
      (node (ref "U4") (pin "1") (pinfunction "IN_1_1") (pintype "passive"))
    )
    (net (code "42") (name "Net-(U5-COM3)") (class "Default")
      (node (ref "R19") (pin "1") (pinfunction "1_1") (pintype "passive"))
      (node (ref "U5") (pin "13") (pinfunction "COM3_13") (pintype "passive"))
    )
    (net (code "43") (name "Net-(U5-COM4)") (class "Default")
      (node (ref "R12") (pin "2") (pinfunction "2_2") (pintype "passive"))
      (node (ref "U5") (pin "18") (pinfunction "COM4_18") (pintype "passive"))
    )
    (net (code "44") (name "Net-(U6A-IN_A+)") (class "Default")
      (node (ref "R15") (pin "1") (pinfunction "1_1") (pintype "passive"))
      (node (ref "R20") (pin "1") (pinfunction "1_1") (pintype "passive"))
      (node (ref "U6") (pin "3") (pinfunction "IN_A+_3") (pintype "input"))
    )
    (net (code "45") (name "Net-(U6B-IN_B+)") (class "Default")
      (node (ref "R14") (pin "1") (pinfunction "1_1") (pintype "passive"))
      (node (ref "R18") (pin "1") (pinfunction "1_1") (pintype "passive"))
      (node (ref "U6") (pin "5") (pinfunction "IN_B+_5") (pintype "input"))
    )
    (net (code "46") (name "Net-(U7-10.0V)") (class "Default")
      (node (ref "C19") (pin "2") (pinfunction "2_2") (pintype "passive"))
      (node (ref "U7") (pin "1") (pinfunction "10.0V_1") (pintype "output"))
      (node (ref "U7") (pin "2") (pinfunction "5.0V_2") (pintype "passive"))
      (node (ref "U8") (pin "3") (pinfunction "IN+_3") (pintype "input"))
    )
    (net (code "47") (name "Net-(U7-CAP)") (class "Default")
      (node (ref "C18") (pin "1") (pinfunction "1_1") (pintype "passive"))
      (node (ref "U7") (pin "7") (pinfunction "CAP_7") (pintype "passive"))
    )
    (net (code "48") (name "Net-(U7-VBG)") (class "Default")
      (node (ref "C18") (pin "2") (pinfunction "2_2") (pintype "passive"))
      (node (ref "U7") (pin "6") (pinfunction "VBG_6") (pintype "passive"))
    )
    (net (code "49") (name "ZH") (class "Default")
      (node (ref "C9") (pin "2") (pinfunction "2_2") (pintype "passive"))
      (node (ref "P2") (pin "8") (pinfunction "8_8") (pintype "passive"))
      (node (ref "P3") (pin "8") (pinfunction "8_8") (pintype "passive"))
      (node (ref "TP7") (pin "1") (pinfunction "1_1") (pintype "input"))
      (node (ref "U3") (pin "1") (pinfunction "10.0V_1") (pintype "output"))
    )
    (net (code "50") (name "ZP") (class "Default")
      (node (ref "C10") (pin "1") (pinfunction "1_1") (pintype "passive"))
      (node (ref "P2") (pin "7") (pinfunction "7_7") (pintype "passive"))
      (node (ref "TP9") (pin "1") (pinfunction "1_1") (pintype "input"))
      (node (ref "U3") (pin "8") (pinfunction "V+_8") (pintype "power_in"))
    )
    (net (code "51") (name "unconnected-(P4-Pad1)") (class "Default")
      (node (ref "P4") (pin "1") (pinfunction "1_1") (pintype "passive"))
    )
    (net (code "52") (name "unconnected-(P4-Pad3)") (class "Default")
      (node (ref "P4") (pin "3") (pinfunction "3_3") (pintype "passive"))
    )
    (net (code "53") (name "unconnected-(P4-Pad4)") (class "Default")
      (node (ref "P4") (pin "4") (pinfunction "4_4") (pintype "passive"))
    )
    (net (code "54") (name "unconnected-(U1-COM1-Pad3)") (class "Default")
      (node (ref "U1") (pin "3") (pinfunction "COM1_3") (pintype "passive+no_connect"))
    )
    (net (code "55") (name "unconnected-(U1-COM2-Pad8)") (class "Default")
      (node (ref "U1") (pin "8") (pinfunction "COM2_8") (pintype "passive+no_connect"))
    )
    (net (code "56") (name "unconnected-(U1-COM4-Pad18)") (class "Default")
      (node (ref "U1") (pin "18") (pinfunction "COM4_18") (pintype "passive+no_connect"))
    )
    (net (code "57") (name "unconnected-(U1-GND-Pad6)") (class "Default")
      (node (ref "U1") (pin "6") (pinfunction "GND_6") (pintype "passive"))
    )
    (net (code "58") (name "unconnected-(U1-IN1-Pad1)") (class "Default")
      (node (ref "U1") (pin "1") (pinfunction "IN1_1") (pintype "passive+no_connect"))
    )
    (net (code "59") (name "unconnected-(U1-IN2-Pad10)") (class "Default")
      (node (ref "U1") (pin "10") (pinfunction "IN2_10") (pintype "passive+no_connect"))
    )
    (net (code "60") (name "unconnected-(U1-IN4-Pad20)") (class "Default")
      (node (ref "U1") (pin "20") (pinfunction "IN4_20") (pintype "passive+no_connect"))
    )
    (net (code "61") (name "unconnected-(U1-N.C.-Pad15)") (class "Default")
      (node (ref "U1") (pin "15") (pinfunction "N.C._15") (pintype "passive+no_connect"))
    )
    (net (code "62") (name "unconnected-(U1-NC1-Pad4)") (class "Default")
      (node (ref "U1") (pin "4") (pinfunction "NC1_4") (pintype "passive+no_connect"))
    )
    (net (code "63") (name "unconnected-(U1-NC2-Pad7)") (class "Default")
      (node (ref "U1") (pin "7") (pinfunction "NC2_7") (pintype "passive+no_connect"))
    )
    (net (code "64") (name "unconnected-(U1-NC4-Pad17)") (class "Default")
      (node (ref "U1") (pin "17") (pinfunction "NC4_17") (pintype "passive+no_connect"))
    )
    (net (code "65") (name "unconnected-(U1-NO1-Pad2)") (class "Default")
      (node (ref "U1") (pin "2") (pinfunction "NO1_2") (pintype "passive+no_connect"))
    )
    (net (code "66") (name "unconnected-(U1-NO2-Pad9)") (class "Default")
      (node (ref "U1") (pin "9") (pinfunction "NO2_9") (pintype "passive+no_connect"))
    )
    (net (code "67") (name "unconnected-(U1-NO4-Pad19)") (class "Default")
      (node (ref "U1") (pin "19") (pinfunction "NO4_19") (pintype "passive+no_connect"))
    )
    (net (code "68") (name "unconnected-(U3-5.0V-Pad2)") (class "Default")
      (node (ref "U3") (pin "2") (pinfunction "5.0V_2") (pintype "output+no_connect"))
    )
    (net (code "69") (name "unconnected-(U3-STROBE-Pad5)") (class "Default")
      (node (ref "U3") (pin "5") (pinfunction "STROBE_5") (pintype "input+no_connect"))
    )
    (net (code "70") (name "unconnected-(U4-OUT_2-Pad4)") (class "Default")
      (node (ref "U4") (pin "4") (pinfunction "OUT_2_4") (pintype "passive+no_connect"))
    )
    (net (code "71") (name "unconnected-(U4-OUT_4-Pad8)") (class "Default")
      (node (ref "U4") (pin "8") (pinfunction "OUT_4_8") (pintype "passive+no_connect"))
    )
    (net (code "72") (name "unconnected-(U4-OUT_5-Pad10)") (class "Default")
      (node (ref "U4") (pin "10") (pinfunction "OUT_5_10") (pintype "passive+no_connect"))
    )
    (net (code "73") (name "unconnected-(U4-OUT_6-Pad12)") (class "Default")
      (node (ref "U4") (pin "12") (pinfunction "OUT_6_12") (pintype "passive+no_connect"))
    )
    (net (code "74") (name "unconnected-(U5-COM1-Pad3)") (class "Default")
      (node (ref "U5") (pin "3") (pinfunction "COM1_3") (pintype "passive"))
    )
    (net (code "75") (name "unconnected-(U5-COM2-Pad8)") (class "Default")
      (node (ref "U5") (pin "8") (pinfunction "COM2_8") (pintype "passive+no_connect"))
    )
    (net (code "76") (name "unconnected-(U5-IN1-Pad1)") (class "Default")
      (node (ref "U5") (pin "1") (pinfunction "IN1_1") (pintype "passive"))
    )
    (net (code "77") (name "unconnected-(U5-IN2-Pad10)") (class "Default")
      (node (ref "U5") (pin "10") (pinfunction "IN2_10") (pintype "passive+no_connect"))
    )
    (net (code "78") (name "unconnected-(U5-N.C.-Pad15)") (class "Default")
      (node (ref "U5") (pin "15") (pinfunction "N.C._15") (pintype "passive+no_connect"))
    )
    (net (code "79") (name "unconnected-(U5-NC1-Pad4)") (class "Default")
      (node (ref "U5") (pin "4") (pinfunction "NC1_4") (pintype "passive"))
    )
    (net (code "80") (name "unconnected-(U5-NC2-Pad7)") (class "Default")
      (node (ref "U5") (pin "7") (pinfunction "NC2_7") (pintype "passive+no_connect"))
    )
    (net (code "81") (name "unconnected-(U5-NO2-Pad9)") (class "Default")
      (node (ref "U5") (pin "9") (pinfunction "NO2_9") (pintype "passive+no_connect"))
    )
    (net (code "82") (name "unconnected-(U7-2.5V-Pad3)") (class "Default")
      (node (ref "U7") (pin "3") (pinfunction "2.5V_3") (pintype "output+no_connect"))
    )
    (net (code "83") (name "unconnected-(U7-STROBE-Pad5)") (class "Default")
      (node (ref "U7") (pin "5") (pinfunction "STROBE_5") (pintype "input+no_connect"))
    )
  )
)
